# MCU_144_IOs.net
KiCad netlist of a schematic drawn in Altium Designer
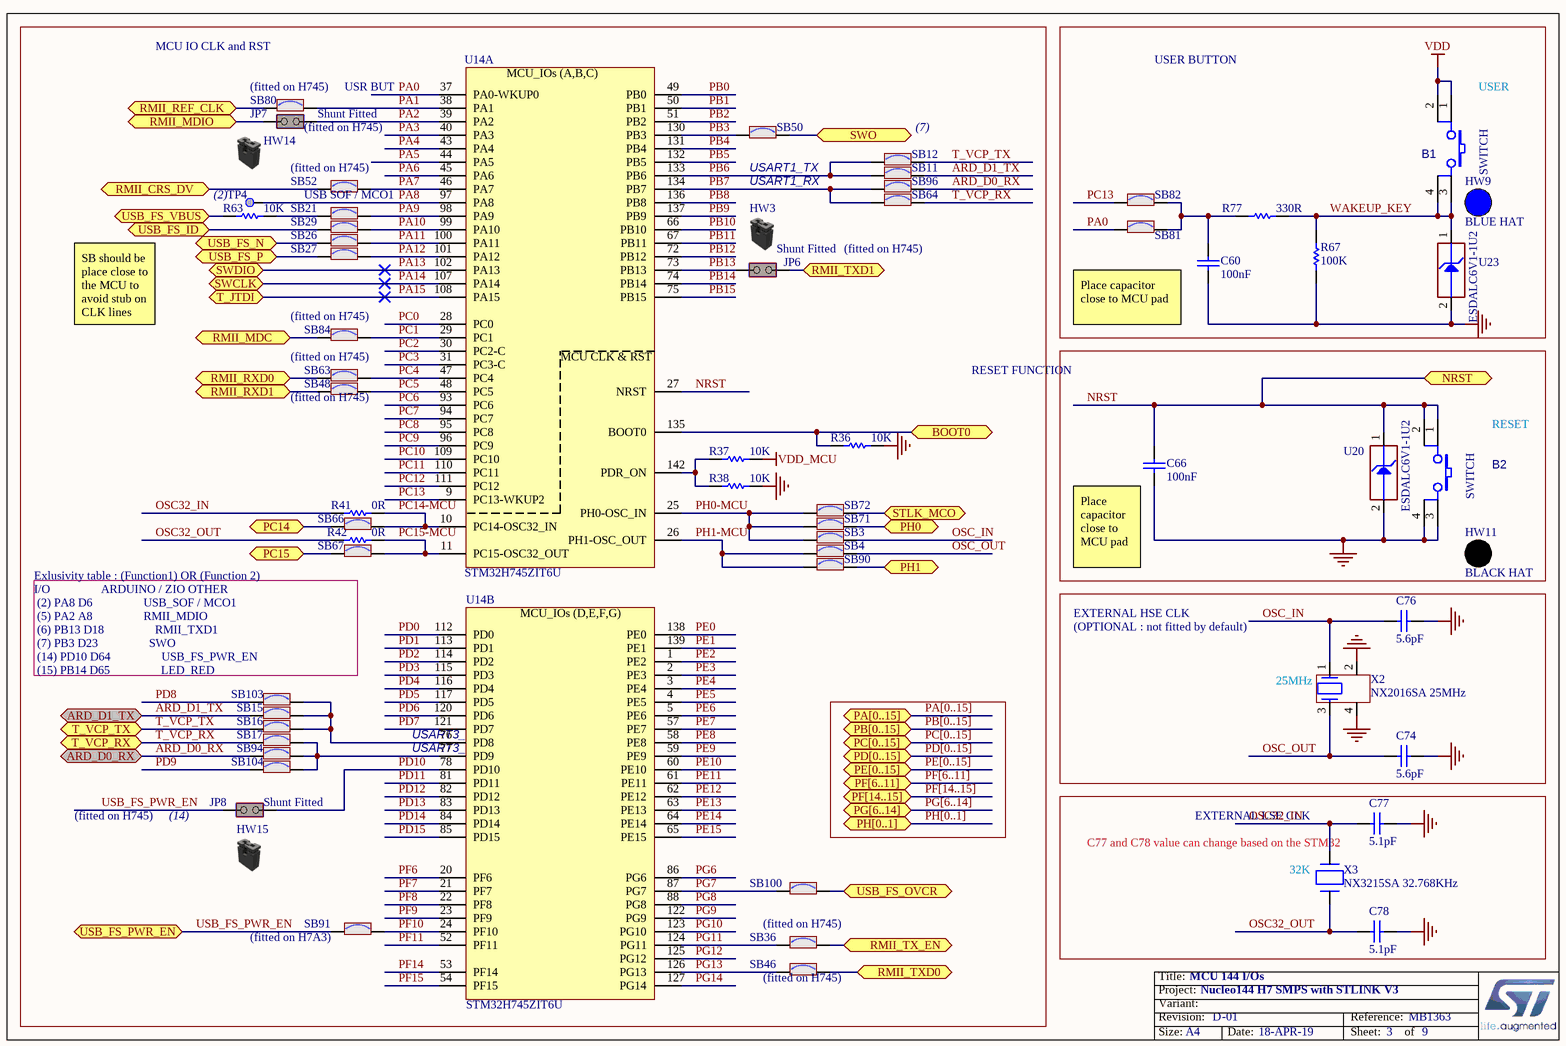
[diagram p0: MCU_144_IOs.SchDoc]

(export (version "E")
  (design (tool "Eeschema 10.0.6"))
  (components
    (comp (ref "B1")
      (value "SWITCH")
      (footprint "SWI_WEALTHMETAL_TD-0341_4P_BLUE")
      (description "Non-Open Push-Button 0.1A 24V")
      (fields
        (field (name "INTERNAL_PART_NUMBER") "MCD-00002")
        (field (name "MANUFACTURER_PART_NUMBER") "TD-0341")
        (field (name "PROVIDED_BY") "SUBCO")
      )
      (libsource (lib "MCD_PARTS_database") (part "SW-PUSH-CMS"))
    )
    (comp (ref "B2")
      (value "SWITCH")
      (footprint "SWI_WEALTHMETAL_TD-0341_4P_BLACK")
      (description "Non-Open Push-Button 0.1A 24V BLACK")
      (fields
        (field (name "INTERNAL_PART_NUMBER") "MCD-00001")
        (field (name "MANUFACTURER_PART_NUMBER") "TD-0341")
        (field (name "PROVIDED_BY") "SUBCO")
      )
      (libsource (lib "MCD_PARTS_database") (part "SW-PUSH-CMS"))
    )
    (comp (ref "C60")
      (value "100nF")
      (footprint "C0603")
      (description "Capacitor, MLCC, 100nF, 6V3, X5R, 10%, 0603, T=0,8mm")
      (fields
        (field (name "INTERNAL_PART_NUMBER") "MCD-00237")
        (field (name "MANUFACTURER_PART_NUMBER") "CC0603KRX5R5BB104")
        (field (name "PROVIDED_BY") "SUBCO")
      )
      (libsource (lib "MCD_PARTS_database") (part "Capacitor"))
    )
    (comp (ref "C66")
      (value "100nF")
      (footprint "C0603")
      (description "Capacitor, MLCC, 100nF, 6V3, X5R, 10%, 0603, T=0,8mm")
      (fields
        (field (name "INTERNAL_PART_NUMBER") "MCD-00237")
        (field (name "MANUFACTURER_PART_NUMBER") "CC0603KRX5R5BB104")
        (field (name "PROVIDED_BY") "SUBCO")
      )
      (libsource (lib "MCD_PARTS_database") (part "Capacitor"))
    )
    (comp (ref "C74")
      (value "5.6pF")
      (footprint "C0402")
      (description "Capacitor, MLCC, 5.6pF, 50V, NPO, 5%, 0402, T=0,5mm")
      (fields
        (field (name "INTERNAL_PART_NUMBER") "MCD-01374")
        (field (name "MANUFACTURER_PART_NUMBER") "CC0402BRNPO9BN5R6")
        (field (name "PROVIDED_BY") "SUBCO")
      )
      (libsource (lib "MCD_PARTS_database") (part "Capacitor"))
    )
    (comp (ref "C76")
      (value "5.6pF")
      (footprint "C0402")
      (description "Capacitor, MLCC, 5.6pF, 50V, NPO, 5%, 0402, T=0,5mm")
      (fields
        (field (name "INTERNAL_PART_NUMBER") "MCD-01374")
        (field (name "MANUFACTURER_PART_NUMBER") "CC0402BRNPO9BN5R6")
        (field (name "PROVIDED_BY") "SUBCO")
      )
      (libsource (lib "MCD_PARTS_database") (part "Capacitor"))
    )
    (comp (ref "C77")
      (value "5.1pF")
      (footprint "C0603")
      (description "Capacitor,5.1pF,0.25pF,50V,NPO,0603")
      (fields
        (field (name "INTERNAL_PART_NUMBER") "MCD-01367")
        (field (name "MANUFACTURER_PART_NUMBER") "CC0603CRNPO9BN5R1")
        (field (name "PROVIDED_BY") "SUBCO")
      )
      (libsource (lib "MCD_PARTS_database") (part "Capacitor"))
    )
    (comp (ref "C78")
      (value "5.1pF")
      (footprint "C0603")
      (description "Capacitor,5.1pF,0.25pF,50V,NPO,0603")
      (fields
        (field (name "INTERNAL_PART_NUMBER") "MCD-01367")
        (field (name "MANUFACTURER_PART_NUMBER") "CC0603CRNPO9BN5R1")
        (field (name "PROVIDED_BY") "SUBCO")
      )
      (libsource (lib "MCD_PARTS_database") (part "Capacitor"))
    )
    (comp (ref "HW3")
      (value "Shunt Black 2.54mm")
      (description "SHUNT 2.54mm BLACK")
      (fields
        (field (name "INTERNAL_PART_NUMBER") "MCD-00043")
        (field (name "MANUFACTURER_PART_NUMBER") "SNT-100-BK-G")
        (field (name "PROVIDED_BY") "SUBCO")
      )
      (libsource (lib "MCD_PARTS_database") (part "Shunt Black 2.54mm"))
    )
    (comp (ref "HW9")
      (value "BLUE HAT")
      (description "Blue Hat for switch TD0341X-G01-BLU")
      (fields
        (field (name "INTERNAL_PART_NUMBER") "MCD-00634")
        (field (name "MANUFACTURER_PART_NUMBER") "988.16.09.3.00002_SH-517")
        (field (name "PROVIDED_BY") "SUBCO")
      )
      (libsource (lib "MCD_PARTS_database") (part "BUTTON_HAT_BLUE"))
    )
    (comp (ref "HW11")
      (value "BLACK HAT")
      (description "Black Hat for switch TD0341X-G01-BLA")
      (fields
        (field (name "INTERNAL_PART_NUMBER") "MCD-00635")
        (field (name "MANUFACTURER_PART_NUMBER") "988.16.09.3.00003_SH-517")
        (field (name "PROVIDED_BY") "SUBCO")
      )
      (libsource (lib "MCD_PARTS_database") (part "BUTTON_HAT_BLACK"))
    )
    (comp (ref "HW14")
      (value "Shunt Black 2.54mm")
      (description "SHUNT 2.54mm BLACK")
      (fields
        (field (name "INTERNAL_PART_NUMBER") "MCD-00043")
        (field (name "MANUFACTURER_PART_NUMBER") "SNT-100-BK-G")
        (field (name "PROVIDED_BY") "SUBCO")
      )
      (libsource (lib "MCD_PARTS_database") (part "Shunt Black 2.54mm"))
    )
    (comp (ref "HW15")
      (value "Shunt Black 2.54mm")
      (description "SHUNT 2.54mm BLACK")
      (fields
        (field (name "INTERNAL_PART_NUMBER") "MCD-00043")
        (field (name "MANUFACTURER_PART_NUMBER") "SNT-100-BK-G")
        (field (name "PROVIDED_BY") "SUBCO")
      )
      (libsource (lib "MCD_PARTS_database") (part "Shunt Black 2.54mm"))
    )
    (comp (ref "JP6")
      (value "Shunt Fitted")
      (footprint "CON_SAMTEC_TSW-102-07-G-S")
      (description "Header, 2x1, 2,54mm, VR, TH, Height 5.84mm/2.54mm - Shunt Fitted by default")
      (fields
        (field (name "INTERNAL_PART_NUMBER") "MCD-00683")
        (field (name "MANUFACTURER_PART_NUMBER") "TSW-102-07-x-S")
        (field (name "PROVIDED_BY") "SUBCO")
      )
      (libsource (lib "MCD_PARTS_database") (part "Jumper_Header 2x1 Fitted"))
    )
    (comp (ref "JP7")
      (value "Shunt Fitted")
      (footprint "CON_SAMTEC_TSW-102-07-G-S")
      (description "Header, 2x1, 2,54mm, VR, TH, Height 5.84mm/2.54mm - Shunt Fitted by default")
      (fields
        (field (name "INTERNAL_PART_NUMBER") "MCD-00683")
        (field (name "MANUFACTURER_PART_NUMBER") "TSW-102-07-x-S")
        (field (name "PROVIDED_BY") "SUBCO")
      )
      (libsource (lib "MCD_PARTS_database") (part "Jumper_Header 2x1 Fitted"))
    )
    (comp (ref "JP8")
      (value "Shunt Fitted")
      (footprint "CON_SAMTEC_TSW-102-07-G-S")
      (description "Header, 2x1, 2,54mm, VR, TH, Height 5.84mm/2.54mm - Shunt Fitted by default")
      (fields
        (field (name "INTERNAL_PART_NUMBER") "MCD-00683")
        (field (name "MANUFACTURER_PART_NUMBER") "TSW-102-07-x-S")
        (field (name "PROVIDED_BY") "SUBCO")
      )
      (libsource (lib "MCD_PARTS_database") (part "Jumper_Header 2x1 Fitted"))
    )
    (comp (ref "R36")
      (value "10K")
      (footprint "R0603")
      (description "Resistor,10K,0603,1%,1/10W")
      (fields
        (field (name "INTERNAL_PART_NUMBER") "MCD-00220")
        (field (name "MANUFACTURER_PART_NUMBER") "RC0603FR-0710KL")
        (field (name "PROVIDED_BY") "SUBCO")
      )
      (libsource (lib "MCD_PARTS_database") (part "Resistor"))
    )
    (comp (ref "R37")
      (value "10K")
      (footprint "R0603")
      (description "Resistor,10K,0603,1%,1/10W")
      (fields
        (field (name "INTERNAL_PART_NUMBER") "MCD-00220")
        (field (name "MANUFACTURER_PART_NUMBER") "RC0603FR-0710KL")
        (field (name "PROVIDED_BY") "SUBCO")
      )
      (libsource (lib "MCD_PARTS_database") (part "Resistor"))
    )
    (comp (ref "R38")
      (value "10K")
      (footprint "R0603")
      (description "Resistor,10K,0603,1%,1/10W")
      (fields
        (field (name "INTERNAL_PART_NUMBER") "MCD-00220")
        (field (name "MANUFACTURER_PART_NUMBER") "RC0603FR-0710KL")
        (field (name "PROVIDED_BY") "SUBCO")
      )
      (libsource (lib "MCD_PARTS_database") (part "Resistor"))
    )
    (comp (ref "R41")
      (value "0R")
      (footprint "R0603")
      (description "Resistor,0R,0603,5%,1/10W")
      (fields
        (field (name "INTERNAL_PART_NUMBER") "MCD-00056")
        (field (name "MANUFACTURER_PART_NUMBER") "RC0603JR-070RL")
        (field (name "PROVIDED_BY") "SUBCO")
      )
      (libsource (lib "MCD_PARTS_database") (part "Resistor"))
    )
    (comp (ref "R42")
      (value "0R")
      (footprint "R0603")
      (description "Resistor,0R,0603,5%,1/10W")
      (fields
        (field (name "INTERNAL_PART_NUMBER") "MCD-00056")
        (field (name "MANUFACTURER_PART_NUMBER") "RC0603JR-070RL")
        (field (name "PROVIDED_BY") "SUBCO")
      )
      (libsource (lib "MCD_PARTS_database") (part "Resistor"))
    )
    (comp (ref "R63")
      (value "10K")
      (footprint "R0402")
      (description "Resistor,10K,0402,1%,1/16W")
      (fields
        (field (name "INTERNAL_PART_NUMBER") "MCD-00053")
        (field (name "MANUFACTURER_PART_NUMBER") "RC0402FR-0710KL")
        (field (name "PROVIDED_BY") "SUBCO")
      )
      (libsource (lib "MCD_PARTS_database") (part "Resistor"))
    )
    (comp (ref "R67")
      (value "100K")
      (footprint "R0603")
      (description "Resistor,100K,0603,1%,1/10W")
      (fields
        (field (name "INTERNAL_PART_NUMBER") "MCD-00223")
        (field (name "MANUFACTURER_PART_NUMBER") "RC0603FR-07100KL")
        (field (name "PROVIDED_BY") "SUBCO")
      )
      (libsource (lib "MCD_PARTS_database") (part "Resistor"))
    )
    (comp (ref "R77")
      (value "330R")
      (footprint "R0603")
      (description "Resistor,330R,0603,1%,1/10W")
      (fields
        (field (name "INTERNAL_PART_NUMBER") "MCD-00197")
        (field (name "MANUFACTURER_PART_NUMBER") "RC0603FR-07330RL")
        (field (name "PROVIDED_BY") "SUBCO")
      )
      (libsource (lib "MCD_PARTS_database") (part "Resistor"))
    )
    (comp (ref "SB3")
      (value "SB_ON")
      (footprint "SOLDER-BRIDGE_R0603-0R")
      (description "Solder Bridge ON")
      (fields
        (field (name "INTERNAL_PART_NUMBER") "MCD-00071")
        (field (name "MANUFACTURER_PART_NUMBER") "RC0603JR-070RL")
        (field (name "PROVIDED_BY") "SUBCO")
      )
      (libsource (lib "MCD_PARTS_database") (part "SB_ON"))
    )
    (comp (ref "SB4")
      (value "SB_ON")
      (footprint "SOLDER-BRIDGE_R0603-0R")
      (description "Solder Bridge ON")
      (fields
        (field (name "INTERNAL_PART_NUMBER") "MCD-00071")
        (field (name "MANUFACTURER_PART_NUMBER") "RC0603JR-070RL")
        (field (name "PROVIDED_BY") "SUBCO")
      )
      (libsource (lib "MCD_PARTS_database") (part "SB_ON"))
    )
    (comp (ref "SB11")
      (value "SB_ON")
      (footprint "SOLDER-BRIDGE_R0603-0R")
      (description "Solder Bridge ON")
      (fields
        (field (name "INTERNAL_PART_NUMBER") "MCD-00071")
        (field (name "MANUFACTURER_PART_NUMBER") "RC0603JR-070RL")
        (field (name "PROVIDED_BY") "SUBCO")
      )
      (libsource (lib "") (part "SB_ON_1"))
    )
    (comp (ref "SB12")
      (value "SB_ON")
      (footprint "SOLDER-BRIDGE_R0603-0R")
      (description "Solder Bridge ON")
      (fields
        (field (name "INTERNAL_PART_NUMBER") "MCD-00071")
        (field (name "MANUFACTURER_PART_NUMBER") "RC0603JR-070RL")
        (field (name "PROVIDED_BY") "SUBCO")
      )
      (libsource (lib "") (part "SB_ON_1"))
    )
    (comp (ref "SB15")
      (value "SB_ON")
      (footprint "SOLDER-BRIDGE_R0603-0R")
      (description "Solder Bridge ON")
      (fields
        (field (name "INTERNAL_PART_NUMBER") "MCD-00071")
        (field (name "MANUFACTURER_PART_NUMBER") "RC0603JR-070RL")
        (field (name "PROVIDED_BY") "SUBCO")
      )
      (libsource (lib "") (part "SB_ON_1"))
    )
    (comp (ref "SB16")
      (value "SB_ON")
      (footprint "SOLDER-BRIDGE_R0603-0R")
      (description "Solder Bridge ON")
      (fields
        (field (name "INTERNAL_PART_NUMBER") "MCD-00071")
        (field (name "MANUFACTURER_PART_NUMBER") "RC0603JR-070RL")
        (field (name "PROVIDED_BY") "SUBCO")
      )
      (libsource (lib "") (part "SB_ON_1"))
    )
    (comp (ref "SB17")
      (value "SB_ON")
      (footprint "SOLDER-BRIDGE_R0603-0R")
      (description "Solder Bridge ON")
      (fields
        (field (name "INTERNAL_PART_NUMBER") "MCD-00071")
        (field (name "MANUFACTURER_PART_NUMBER") "RC0603JR-070RL")
        (field (name "PROVIDED_BY") "SUBCO")
      )
      (libsource (lib "") (part "SB_ON_1"))
    )
    (comp (ref "SB21")
      (value "SB_ON")
      (footprint "SOLDER-BRIDGE_R0603-0R")
      (description "Solder Bridge ON")
      (fields
        (field (name "INTERNAL_PART_NUMBER") "MCD-00071")
        (field (name "MANUFACTURER_PART_NUMBER") "RC0603JR-070RL")
        (field (name "PROVIDED_BY") "SUBCO")
      )
      (libsource (lib "") (part "SB_ON_1"))
    )
    (comp (ref "SB26")
      (value "SB_ON")
      (footprint "SOLDER-BRIDGE_R0603-0R")
      (description "Solder Bridge ON")
      (fields
        (field (name "INTERNAL_PART_NUMBER") "MCD-00071")
        (field (name "MANUFACTURER_PART_NUMBER") "RC0603JR-070RL")
        (field (name "PROVIDED_BY") "SUBCO")
      )
      (libsource (lib "") (part "SB_ON_1"))
    )
    (comp (ref "SB27")
      (value "SB_ON")
      (footprint "SOLDER-BRIDGE_R0603-0R")
      (description "Solder Bridge ON")
      (fields
        (field (name "INTERNAL_PART_NUMBER") "MCD-00071")
        (field (name "MANUFACTURER_PART_NUMBER") "RC0603JR-070RL")
        (field (name "PROVIDED_BY") "SUBCO")
      )
      (libsource (lib "") (part "SB_ON_1"))
    )
    (comp (ref "SB29")
      (value "SB_ON")
      (footprint "SOLDER-BRIDGE_R0603-0R")
      (description "Solder Bridge ON")
      (fields
        (field (name "INTERNAL_PART_NUMBER") "MCD-00071")
        (field (name "MANUFACTURER_PART_NUMBER") "RC0603JR-070RL")
        (field (name "PROVIDED_BY") "SUBCO")
      )
      (libsource (lib "") (part "SB_ON_1"))
    )
    (comp (ref "SB36")
      (value "SB_ON")
      (footprint "SOLDER-BRIDGE_R0603-0R")
      (description "Solder Bridge ON")
      (fields
        (field (name "INTERNAL_PART_NUMBER") "MCD-00071")
        (field (name "MANUFACTURER_PART_NUMBER") "RC0603JR-070RL")
        (field (name "PROVIDED_BY") "SUBCO")
      )
      (libsource (lib "") (part "SB_ON_1"))
    )
    (comp (ref "SB46")
      (value "SB_ON")
      (footprint "SOLDER-BRIDGE_R0603-0R")
      (description "Solder Bridge ON")
      (fields
        (field (name "INTERNAL_PART_NUMBER") "MCD-00071")
        (field (name "MANUFACTURER_PART_NUMBER") "RC0603JR-070RL")
        (field (name "PROVIDED_BY") "SUBCO")
      )
      (libsource (lib "") (part "SB_ON_1"))
    )
    (comp (ref "SB48")
      (value "SB_ON")
      (footprint "SOLDER-BRIDGE_R0603-0R")
      (description "Solder Bridge ON")
      (fields
        (field (name "INTERNAL_PART_NUMBER") "MCD-00071")
        (field (name "MANUFACTURER_PART_NUMBER") "RC0603JR-070RL")
        (field (name "PROVIDED_BY") "SUBCO")
      )
      (libsource (lib "MCD_PARTS_database") (part "SB_ON"))
    )
    (comp (ref "SB50")
      (value "SB_ON")
      (footprint "SOLDER-BRIDGE_R0603-0R")
      (description "Solder Bridge ON")
      (fields
        (field (name "INTERNAL_PART_NUMBER") "MCD-00071")
        (field (name "MANUFACTURER_PART_NUMBER") "RC0603JR-070RL")
        (field (name "PROVIDED_BY") "SUBCO")
      )
      (libsource (lib "") (part "SB_ON_1"))
    )
    (comp (ref "SB52")
      (value "SB_ON")
      (footprint "SOLDER-BRIDGE_R0603-0R")
      (description "Solder Bridge ON")
      (fields
        (field (name "INTERNAL_PART_NUMBER") "MCD-00071")
        (field (name "MANUFACTURER_PART_NUMBER") "RC0603JR-070RL")
        (field (name "PROVIDED_BY") "SUBCO")
      )
      (libsource (lib "") (part "SB_ON_1"))
    )
    (comp (ref "SB63")
      (value "SB_ON")
      (footprint "SOLDER-BRIDGE_R0603-0R")
      (description "Solder Bridge ON")
      (fields
        (field (name "INTERNAL_PART_NUMBER") "MCD-00071")
        (field (name "MANUFACTURER_PART_NUMBER") "RC0603JR-070RL")
        (field (name "PROVIDED_BY") "SUBCO")
      )
      (libsource (lib "MCD_PARTS_database") (part "SB_ON"))
    )
    (comp (ref "SB64")
      (value "SB_ON")
      (footprint "SOLDER-BRIDGE_R0603-0R")
      (description "Solder Bridge ON")
      (fields
        (field (name "INTERNAL_PART_NUMBER") "MCD-00071")
        (field (name "MANUFACTURER_PART_NUMBER") "RC0603JR-070RL")
        (field (name "PROVIDED_BY") "SUBCO")
      )
      (libsource (lib "") (part "SB_ON_1"))
    )
    (comp (ref "SB66")
      (value "SB_ON")
      (footprint "SOLDER-BRIDGE_R0603-0R")
      (description "Solder Bridge ON")
      (fields
        (field (name "INTERNAL_PART_NUMBER") "MCD-00071")
        (field (name "MANUFACTURER_PART_NUMBER") "RC0603JR-070RL")
        (field (name "PROVIDED_BY") "SUBCO")
      )
      (libsource (lib "MCD_PARTS_database") (part "SB_ON"))
    )
    (comp (ref "SB67")
      (value "SB_ON")
      (footprint "SOLDER-BRIDGE_R0603-0R")
      (description "Solder Bridge ON")
      (fields
        (field (name "INTERNAL_PART_NUMBER") "MCD-00071")
        (field (name "MANUFACTURER_PART_NUMBER") "RC0603JR-070RL")
        (field (name "PROVIDED_BY") "SUBCO")
      )
      (libsource (lib "MCD_PARTS_database") (part "SB_ON"))
    )
    (comp (ref "SB71")
      (value "SB_ON")
      (footprint "SOLDER-BRIDGE_R0603-0R")
      (description "Solder Bridge ON")
      (fields
        (field (name "INTERNAL_PART_NUMBER") "MCD-00071")
        (field (name "MANUFACTURER_PART_NUMBER") "RC0603JR-070RL")
        (field (name "PROVIDED_BY") "SUBCO")
      )
      (libsource (lib "MCD_PARTS_database") (part "SB_ON"))
    )
    (comp (ref "SB72")
      (value "SB_ON")
      (footprint "SOLDER-BRIDGE_R0603-0R")
      (description "Solder Bridge ON")
      (fields
        (field (name "INTERNAL_PART_NUMBER") "MCD-00071")
        (field (name "MANUFACTURER_PART_NUMBER") "RC0603JR-070RL")
        (field (name "PROVIDED_BY") "SUBCO")
      )
      (libsource (lib "MCD_PARTS_database") (part "SB_ON"))
    )
    (comp (ref "SB80")
      (value "SB_ON")
      (footprint "SOLDER-BRIDGE_R0603-0R")
      (description "Solder Bridge ON")
      (fields
        (field (name "INTERNAL_PART_NUMBER") "MCD-00071")
        (field (name "MANUFACTURER_PART_NUMBER") "RC0603JR-070RL")
        (field (name "PROVIDED_BY") "SUBCO")
      )
      (libsource (lib "") (part "SB_ON_1"))
    )
    (comp (ref "SB81")
      (value "SB_ON")
      (footprint "SOLDER-BRIDGE_R0603-0R")
      (description "Solder Bridge ON")
      (fields
        (field (name "INTERNAL_PART_NUMBER") "MCD-00071")
        (field (name "MANUFACTURER_PART_NUMBER") "RC0603JR-070RL")
        (field (name "PROVIDED_BY") "SUBCO")
      )
      (libsource (lib "") (part "SB_ON_1"))
    )
    (comp (ref "SB82")
      (value "SB_ON")
      (footprint "SOLDER-BRIDGE_R0603-0R")
      (description "Solder Bridge ON")
      (fields
        (field (name "INTERNAL_PART_NUMBER") "MCD-00071")
        (field (name "MANUFACTURER_PART_NUMBER") "RC0603JR-070RL")
        (field (name "PROVIDED_BY") "SUBCO")
      )
      (libsource (lib "") (part "SB_ON_1"))
    )
    (comp (ref "SB84")
      (value "SB_ON")
      (footprint "SOLDER-BRIDGE_R0603-0R")
      (description "Solder Bridge ON")
      (fields
        (field (name "INTERNAL_PART_NUMBER") "MCD-00071")
        (field (name "MANUFACTURER_PART_NUMBER") "RC0603JR-070RL")
        (field (name "PROVIDED_BY") "SUBCO")
      )
      (libsource (lib "MCD_PARTS_database") (part "SB_ON"))
    )
    (comp (ref "SB90")
      (value "SB_ON")
      (footprint "SOLDER-BRIDGE_R0603-0R")
      (description "Solder Bridge ON")
      (fields
        (field (name "INTERNAL_PART_NUMBER") "MCD-00071")
        (field (name "MANUFACTURER_PART_NUMBER") "RC0603JR-070RL")
        (field (name "PROVIDED_BY") "SUBCO")
      )
      (libsource (lib "MCD_PARTS_database") (part "SB_ON"))
    )
    (comp (ref "SB91")
      (value "SB_ON")
      (footprint "SOLDER-BRIDGE_R0603-0R")
      (description "Solder Bridge ON")
      (fields
        (field (name "INTERNAL_PART_NUMBER") "MCD-00071")
        (field (name "MANUFACTURER_PART_NUMBER") "RC0603JR-070RL")
        (field (name "PROVIDED_BY") "SUBCO")
      )
      (libsource (lib "") (part "SB_ON_1"))
    )
    (comp (ref "SB94")
      (value "SB_ON")
      (footprint "SOLDER-BRIDGE_R0603-0R")
      (description "Solder Bridge ON")
      (fields
        (field (name "INTERNAL_PART_NUMBER") "MCD-00071")
        (field (name "MANUFACTURER_PART_NUMBER") "RC0603JR-070RL")
        (field (name "PROVIDED_BY") "SUBCO")
      )
      (libsource (lib "") (part "SB_ON_1"))
    )
    (comp (ref "SB96")
      (value "SB_ON")
      (footprint "SOLDER-BRIDGE_R0603-0R")
      (description "Solder Bridge ON")
      (fields
        (field (name "INTERNAL_PART_NUMBER") "MCD-00071")
        (field (name "MANUFACTURER_PART_NUMBER") "RC0603JR-070RL")
        (field (name "PROVIDED_BY") "SUBCO")
      )
      (libsource (lib "") (part "SB_ON_1"))
    )
    (comp (ref "SB100")
      (value "SB_ON")
      (footprint "SOLDER-BRIDGE_R0603-0R")
      (description "Solder Bridge ON")
      (fields
        (field (name "INTERNAL_PART_NUMBER") "MCD-00071")
        (field (name "MANUFACTURER_PART_NUMBER") "RC0603JR-070RL")
        (field (name "PROVIDED_BY") "SUBCO")
      )
      (libsource (lib "") (part "SB_ON_1"))
    )
    (comp (ref "SB103")
      (value "SB_ON")
      (footprint "SOLDER-BRIDGE_R0603-0R")
      (description "Solder Bridge ON")
      (fields
        (field (name "INTERNAL_PART_NUMBER") "MCD-00071")
        (field (name "MANUFACTURER_PART_NUMBER") "RC0603JR-070RL")
        (field (name "PROVIDED_BY") "SUBCO")
      )
      (libsource (lib "MCD_PARTS_database") (part "SB_ON"))
    )
    (comp (ref "SB104")
      (value "SB_ON")
      (footprint "SOLDER-BRIDGE_R0603-0R")
      (description "Solder Bridge ON")
      (fields
        (field (name "INTERNAL_PART_NUMBER") "MCD-00071")
        (field (name "MANUFACTURER_PART_NUMBER") "RC0603JR-070RL")
        (field (name "PROVIDED_BY") "SUBCO")
      )
      (libsource (lib "MCD_PARTS_database") (part "SB_ON"))
    )
    (comp (ref "TP4")
      (value "Test Point")
      (footprint "TP_SMD_1MM")
      (description "Test Point 1mm")
      (fields
        (field (name "INTERNAL_PART_NUMBER") "MCD-00074")
        (field (name "MANUFACTURER_PART_NUMBER") "n/a")
      )
      (libsource (lib "MCD_PARTS_database") (part "Test Point"))
    )
    (comp (ref "U14")
      (value "STM32H745ZIT6U")
      (footprint "ICC_LQFP144_20X20_P050_SOCKET_YAMAICHI_IC149-144-145-B5_NM")
      (description "STM32H745ZIT6U, LQFP144 package, 20x20, with socket footprint")
      (fields
        (field (name "INTERNAL_PART_NUMBER") "MCD-01401")
        (field (name "MANUFACTURER") "STMICROELECTRONICS")
        (field (name "PROVIDED_BY") "SUBCO with ST control")
      )
      (libsource (lib "MCD_PARTS_database") (part "STM32H7_LQFP144_SMPS"))
    )
    (comp (ref "U20")
      (value "ESDALC6V1-1U2")
      (footprint "ESD_ST0201")
      (description "ESD protection 6V1")
      (fields
        (field (name "INTERNAL_PART_NUMBER") "MCD-00170")
        (field (name "MANUFACTURER") "STMICROELECTRONICS")
        (field (name "PROVIDED_BY") "SUBCO with ST control")
      )
      (libsource (lib "MCD_PARTS_database") (part "ESD-TRANSIL"))
    )
    (comp (ref "U23")
      (value "ESDALC6V1-1U2")
      (footprint "ESD_ST0201")
      (description "ESD protection 6V1")
      (fields
        (field (name "INTERNAL_PART_NUMBER") "MCD-00170")
        (field (name "MANUFACTURER") "STMICROELECTRONICS")
        (field (name "PROVIDED_BY") "SUBCO with ST control")
      )
      (libsource (lib "MCD_PARTS_database") (part "ESD-TRANSIL"))
    )
    (comp (ref "X2")
      (value "NX2016SA 25MHz")
      (footprint "CRY_NX2016SA_4P")
      (description "Crystal 25MHz, 6pF, +-20ppm, 80ohms max, SMD")
      (fields
        (field (name "INTERNAL_PART_NUMBER") "MCD-01364")
        (field (name "MANUFACTURER_PART_NUMBER") "NX2016SA 25MHz EXS00A-CS11321")
        (field (name "PROVIDED_BY") "SUBCO")
      )
      (libsource (lib "MCD_PARTS_database") (part "XTAL_4_PINS"))
    )
    (comp (ref "X3")
      (value "NX3215SA 32.768KHz")
      (footprint "CRY_NX3215SA_2P")
      (description "Crystal 32.768kHz, 6pF, +-20ppm, 50Kohms max, SMD")
      (fields
        (field (name "INTERNAL_PART_NUMBER") "MCD-00091")
        (field (name "MANUFACTURER_PART_NUMBER") "NX3215SA 32.768KHz EXS00A-MU00525")
        (field (name "PROVIDED_BY") "SUBCO")
      )
      (libsource (lib "MCD_PARTS_database") (part "XTAL_2_PINS"))
    )
  )
  (nets
    (net (code "1") (name "/ARD_D0_RX") (class "Default")
      (node (ref "SB94") (pin "2") (pinfunction "2_2") (pintype "passive"))
      (node (ref "SB96") (pin "1") (pinfunction "1_1") (pintype "passive"))
    )
    (net (code "2") (name "/ARD_D1_TX") (class "Default")
      (node (ref "SB11") (pin "1") (pinfunction "1_1") (pintype "passive"))
      (node (ref "SB15") (pin "2") (pinfunction "2_2") (pintype "passive"))
    )
    (net (code "3") (name "/BOOT0") (class "Default")
      (node (ref "R36") (pin "1") (pinfunction "1_1") (pintype "passive"))
      (node (ref "U14") (pin "135") (pinfunction "BOOT0_135") (pintype "passive"))
    )
    (net (code "4") (name "/NRST") (class "Default")
      (node (ref "B2") (pin "1") (pinfunction "1_1") (pintype "passive"))
      (node (ref "B2") (pin "2") (pinfunction "2_2") (pintype "passive"))
      (node (ref "C66") (pin "2") (pinfunction "2_2") (pintype "passive"))
      (node (ref "U14") (pin "27") (pinfunction "NRST_27") (pintype "passive"))
      (node (ref "U20") (pin "1") (pinfunction "IO1_1") (pintype "passive"))
    )
    (net (code "5") (name "/OSC32_IN") (class "Default")
      (node (ref "C77") (pin "1") (pinfunction "1_1") (pintype "passive"))
      (node (ref "R41") (pin "2") (pinfunction "2_2") (pintype "passive"))
      (node (ref "X3") (pin "2") (pinfunction "X2_2") (pintype "passive"))
    )
    (net (code "6") (name "/OSC32_OUT") (class "Default")
      (node (ref "C78") (pin "1") (pinfunction "1_1") (pintype "passive"))
      (node (ref "R42") (pin "1") (pinfunction "1_1") (pintype "passive"))
      (node (ref "X3") (pin "1") (pinfunction "X1_1") (pintype "passive"))
    )
    (net (code "7") (name "/OSC_IN") (class "Default")
      (node (ref "C76") (pin "1") (pinfunction "1_1") (pintype "passive"))
      (node (ref "SB3") (pin "2") (pinfunction "2_2") (pintype "passive"))
      (node (ref "X2") (pin "1") (pinfunction "1_1") (pintype "passive"))
    )
    (net (code "8") (name "/OSC_OUT") (class "Default")
      (node (ref "C74") (pin "1") (pinfunction "1_1") (pintype "passive"))
      (node (ref "SB4") (pin "2") (pinfunction "2_2") (pintype "passive"))
      (node (ref "X2") (pin "3") (pinfunction "3_3") (pintype "passive"))
    )
    (net (code "9") (name "/PA0") (class "Default")
      (node (ref "SB81") (pin "2") (pinfunction "2_2") (pintype "passive"))
      (node (ref "U14") (pin "37") (pinfunction "PA0-WKUP0_37") (pintype "passive"))
    )
    (net (code "10") (name "/PA1") (class "Default")
      (node (ref "SB80") (pin "1") (pinfunction "1_1") (pintype "passive"))
      (node (ref "U14") (pin "38") (pinfunction "PA1_38") (pintype "passive"))
    )
    (net (code "11") (name "/PA2") (class "Default")
      (node (ref "JP7") (pin "2") (pinfunction "NO_2") (pintype "passive"))
      (node (ref "U14") (pin "39") (pinfunction "PA2_39") (pintype "passive"))
    )
    (net (code "12") (name "/PA3") (class "Default")
      (node (ref "U14") (pin "40") (pinfunction "PA3_40") (pintype "passive"))
    )
    (net (code "13") (name "/PA4") (class "Default")
      (node (ref "U14") (pin "43") (pinfunction "PA4_43") (pintype "passive"))
    )
    (net (code "14") (name "/PA5") (class "Default")
      (node (ref "U14") (pin "44") (pinfunction "PA5_44") (pintype "passive"))
    )
    (net (code "15") (name "/PA6") (class "Default")
      (node (ref "U14") (pin "45") (pinfunction "PA6_45") (pintype "passive"))
    )
    (net (code "16") (name "/PA7") (class "Default")
      (node (ref "SB52") (pin "1") (pinfunction "1_1") (pintype "passive"))
      (node (ref "U14") (pin "46") (pinfunction "PA7_46") (pintype "passive"))
    )
    (net (code "17") (name "/PA8") (class "Default")
      (node (ref "TP4") (pin "1") (pinfunction "1_1") (pintype "passive"))
      (node (ref "U14") (pin "97") (pinfunction "PA8_97") (pintype "passive"))
    )
    (net (code "18") (name "/PA9") (class "Default")
      (node (ref "SB21") (pin "1") (pinfunction "1_1") (pintype "passive"))
      (node (ref "U14") (pin "98") (pinfunction "PA9_98") (pintype "passive"))
    )
    (net (code "19") (name "/PA10") (class "Default")
      (node (ref "SB29") (pin "1") (pinfunction "1_1") (pintype "passive"))
      (node (ref "U14") (pin "99") (pinfunction "PA10_99") (pintype "passive"))
    )
    (net (code "20") (name "/PA11") (class "Default")
      (node (ref "SB26") (pin "1") (pinfunction "1_1") (pintype "passive"))
      (node (ref "U14") (pin "100") (pinfunction "PA11_100") (pintype "passive"))
    )
    (net (code "21") (name "/PA12") (class "Default")
      (node (ref "SB27") (pin "1") (pinfunction "1_1") (pintype "passive"))
      (node (ref "U14") (pin "101") (pinfunction "PA12_101") (pintype "passive"))
    )
    (net (code "22") (name "/PA13") (class "Default")
      (node (ref "U14") (pin "102") (pinfunction "PA13_102") (pintype "passive"))
    )
    (net (code "23") (name "/PA14") (class "Default")
      (node (ref "U14") (pin "107") (pinfunction "PA14_107") (pintype "passive"))
    )
    (net (code "24") (name "/PA15") (class "Default")
      (node (ref "U14") (pin "108") (pinfunction "PA15_108") (pintype "passive"))
    )
    (net (code "26") (name "/PB0") (class "Default")
      (node (ref "U14") (pin "49") (pinfunction "PB0_49") (pintype "passive"))
    )
    (net (code "27") (name "/PB1") (class "Default")
      (node (ref "U14") (pin "50") (pinfunction "PB1_50") (pintype "passive"))
    )
    (net (code "28") (name "/PB2") (class "Default")
      (node (ref "U14") (pin "51") (pinfunction "PB2_51") (pintype "passive"))
    )
    (net (code "29") (name "/PB3") (class "Default")
      (node (ref "SB50") (pin "2") (pinfunction "2_2") (pintype "passive"))
      (node (ref "U14") (pin "130") (pinfunction "PB3_130") (pintype "passive"))
    )
    (net (code "30") (name "/PB4") (class "Default")
      (node (ref "U14") (pin "131") (pinfunction "PB4_131") (pintype "passive"))
    )
    (net (code "31") (name "/PB5") (class "Default")
      (node (ref "U14") (pin "132") (pinfunction "PB5_132") (pintype "passive"))
    )
    (net (code "32") (name "/PB6") (class "Default")
      (node (ref "SB11") (pin "2") (pinfunction "2_2") (pintype "passive"))
      (node (ref "SB12") (pin "2") (pinfunction "2_2") (pintype "passive"))
      (node (ref "U14") (pin "133") (pinfunction "PB6_133") (pintype "passive"))
    )
    (net (code "33") (name "/PB7") (class "Default")
      (node (ref "SB64") (pin "2") (pinfunction "2_2") (pintype "passive"))
      (node (ref "SB96") (pin "2") (pinfunction "2_2") (pintype "passive"))
      (node (ref "U14") (pin "134") (pinfunction "PB7_134") (pintype "passive"))
    )
    (net (code "34") (name "/PB8") (class "Default")
      (node (ref "U14") (pin "136") (pinfunction "PB8_136") (pintype "passive"))
    )
    (net (code "35") (name "/PB9") (class "Default")
      (node (ref "U14") (pin "137") (pinfunction "PB9_137") (pintype "passive"))
    )
    (net (code "36") (name "/PB10") (class "Default")
      (node (ref "U14") (pin "66") (pinfunction "PB10_66") (pintype "passive"))
    )
    (net (code "37") (name "/PB11") (class "Default")
      (node (ref "U14") (pin "67") (pinfunction "PB11_67") (pintype "passive"))
    )
    (net (code "38") (name "/PB12") (class "Default")
      (node (ref "U14") (pin "72") (pinfunction "PB12_72") (pintype "passive"))
    )
    (net (code "39") (name "/PB13") (class "Default")
      (node (ref "JP6") (pin "1") (pinfunction "COMMON_1") (pintype "passive"))
      (node (ref "U14") (pin "73") (pinfunction "PB13_73") (pintype "passive"))
    )
    (net (code "40") (name "/PB14") (class "Default")
      (node (ref "U14") (pin "74") (pinfunction "PB14_74") (pintype "passive"))
    )
    (net (code "41") (name "/PB15") (class "Default")
      (node (ref "U14") (pin "75") (pinfunction "PB15_75") (pintype "passive"))
    )
    (net (code "43") (name "/PC0") (class "Default")
      (node (ref "U14") (pin "28") (pinfunction "PC0_28") (pintype "passive"))
    )
    (net (code "44") (name "/PC1") (class "Default")
      (node (ref "SB84") (pin "2") (pinfunction "2_2") (pintype "passive"))
      (node (ref "U14") (pin "29") (pinfunction "PC1_29") (pintype "passive"))
    )
    (net (code "45") (name "/PC2") (class "Default")
      (node (ref "U14") (pin "30") (pinfunction "PC2-C_30") (pintype "passive"))
    )
    (net (code "46") (name "/PC3") (class "Default")
      (node (ref "U14") (pin "31") (pinfunction "PC3-C_31") (pintype "passive"))
    )
    (net (code "47") (name "/PC4") (class "Default")
      (node (ref "SB63") (pin "2") (pinfunction "2_2") (pintype "passive"))
      (node (ref "U14") (pin "47") (pinfunction "PC4_47") (pintype "passive"))
    )
    (net (code "48") (name "/PC5") (class "Default")
      (node (ref "SB48") (pin "2") (pinfunction "2_2") (pintype "passive"))
      (node (ref "U14") (pin "48") (pinfunction "PC5_48") (pintype "passive"))
    )
    (net (code "49") (name "/PC6") (class "Default")
      (node (ref "U14") (pin "93") (pinfunction "PC6_93") (pintype "passive"))
    )
    (net (code "50") (name "/PC7") (class "Default")
      (node (ref "U14") (pin "94") (pinfunction "PC7_94") (pintype "passive"))
    )
    (net (code "51") (name "/PC8") (class "Default")
      (node (ref "U14") (pin "95") (pinfunction "PC8_95") (pintype "passive"))
    )
    (net (code "52") (name "/PC9") (class "Default")
      (node (ref "U14") (pin "96") (pinfunction "PC9_96") (pintype "passive"))
    )
    (net (code "53") (name "/PC10") (class "Default")
      (node (ref "U14") (pin "109") (pinfunction "PC10_109") (pintype "passive"))
    )
    (net (code "54") (name "/PC11") (class "Default")
      (node (ref "U14") (pin "110") (pinfunction "PC11_110") (pintype "passive"))
    )
    (net (code "55") (name "/PC12") (class "Default")
      (node (ref "U14") (pin "111") (pinfunction "PC12_111") (pintype "passive"))
    )
    (net (code "56") (name "/PC13") (class "Default")
      (node (ref "SB82") (pin "2") (pinfunction "2_2") (pintype "passive"))
      (node (ref "U14") (pin "9") (pinfunction "PC13-WKUP2_9") (pintype "passive"))
    )
    (net (code "57") (name "/PC14") (class "Default")
      (node (ref "SB66") (pin "1") (pinfunction "1_1") (pintype "passive"))
    )
    (net (code "58") (name "/PC14-MCU") (class "Default")
      (node (ref "R41") (pin "1") (pinfunction "1_1") (pintype "passive"))
      (node (ref "SB66") (pin "2") (pinfunction "2_2") (pintype "passive"))
      (node (ref "U14") (pin "10") (pinfunction "PC14-OSC32_IN_10") (pintype "passive"))
    )
    (net (code "59") (name "/PC15") (class "Default")
      (node (ref "SB67") (pin "1") (pinfunction "1_1") (pintype "passive"))
    )
    (net (code "60") (name "/PC15-MCU") (class "Default")
      (node (ref "R42") (pin "2") (pinfunction "2_2") (pintype "passive"))
      (node (ref "SB67") (pin "2") (pinfunction "2_2") (pintype "passive"))
      (node (ref "U14") (pin "11") (pinfunction "PC15-OSC32_OUT_11") (pintype "passive"))
    )
    (net (code "62") (name "/PD0") (class "Default")
      (node (ref "U14") (pin "112") (pinfunction "PD0_112") (pintype "passive"))
    )
    (net (code "63") (name "/PD1") (class "Default")
      (node (ref "U14") (pin "113") (pinfunction "PD1_113") (pintype "passive"))
    )
    (net (code "64") (name "/PD2") (class "Default")
      (node (ref "U14") (pin "114") (pinfunction "PD2_114") (pintype "passive"))
    )
    (net (code "65") (name "/PD3") (class "Default")
      (node (ref "U14") (pin "115") (pinfunction "PD3_115") (pintype "passive"))
    )
    (net (code "66") (name "/PD4") (class "Default")
      (node (ref "U14") (pin "116") (pinfunction "PD4_116") (pintype "passive"))
    )
    (net (code "67") (name "/PD5") (class "Default")
      (node (ref "U14") (pin "117") (pinfunction "PD5_117") (pintype "passive"))
    )
    (net (code "68") (name "/PD6") (class "Default")
      (node (ref "U14") (pin "120") (pinfunction "PD6_120") (pintype "passive"))
    )
    (net (code "69") (name "/PD7") (class "Default")
      (node (ref "U14") (pin "121") (pinfunction "PD7_121") (pintype "passive"))
    )
    (net (code "70") (name "/PD8") (class "Default")
      (node (ref "SB103") (pin "1") (pinfunction "1_1") (pintype "passive"))
    )
    (net (code "71") (name "/PD9") (class "Default")
      (node (ref "SB104") (pin "1") (pinfunction "1_1") (pintype "passive"))
    )
    (net (code "72") (name "/PD10") (class "Default")
      (node (ref "JP8") (pin "2") (pinfunction "NO_2") (pintype "passive"))
      (node (ref "U14") (pin "78") (pinfunction "PD10_78") (pintype "passive"))
    )
    (net (code "73") (name "/PD11") (class "Default")
      (node (ref "U14") (pin "81") (pinfunction "PD11_81") (pintype "passive"))
    )
    (net (code "74") (name "/PD12") (class "Default")
      (node (ref "U14") (pin "82") (pinfunction "PD12_82") (pintype "passive"))
    )
    (net (code "75") (name "/PD13") (class "Default")
      (node (ref "U14") (pin "83") (pinfunction "PD13_83") (pintype "passive"))
    )
    (net (code "76") (name "/PD14") (class "Default")
      (node (ref "U14") (pin "84") (pinfunction "PD14_84") (pintype "passive"))
    )
    (net (code "77") (name "/PD15") (class "Default")
      (node (ref "U14") (pin "85") (pinfunction "PD15_85") (pintype "passive"))
    )
    (net (code "79") (name "/PE0") (class "Default")
      (node (ref "U14") (pin "138") (pinfunction "PE0_138") (pintype "passive"))
    )
    (net (code "80") (name "/PE1") (class "Default")
      (node (ref "U14") (pin "139") (pinfunction "PE1_139") (pintype "passive"))
    )
    (net (code "81") (name "/PE2") (class "Default")
      (node (ref "U14") (pin "1") (pinfunction "PE2_1") (pintype "passive"))
    )
    (net (code "82") (name "/PE3") (class "Default")
      (node (ref "U14") (pin "2") (pinfunction "PE3_2") (pintype "passive"))
    )
    (net (code "83") (name "/PE4") (class "Default")
      (node (ref "U14") (pin "3") (pinfunction "PE4_3") (pintype "passive"))
    )
    (net (code "84") (name "/PE5") (class "Default")
      (node (ref "U14") (pin "4") (pinfunction "PE5_4") (pintype "passive"))
    )
    (net (code "85") (name "/PE6") (class "Default")
      (node (ref "U14") (pin "5") (pinfunction "PE6_5") (pintype "passive"))
    )
    (net (code "86") (name "/PE7") (class "Default")
      (node (ref "U14") (pin "57") (pinfunction "PE7_57") (pintype "passive"))
    )
    (net (code "87") (name "/PE8") (class "Default")
      (node (ref "U14") (pin "58") (pinfunction "PE8_58") (pintype "passive"))
    )
    (net (code "88") (name "/PE9") (class "Default")
      (node (ref "U14") (pin "59") (pinfunction "PE9_59") (pintype "passive"))
    )
    (net (code "89") (name "/PE10") (class "Default")
      (node (ref "U14") (pin "60") (pinfunction "PE10_60") (pintype "passive"))
    )
    (net (code "90") (name "/PE11") (class "Default")
      (node (ref "U14") (pin "61") (pinfunction "PE11_61") (pintype "passive"))
    )
    (net (code "91") (name "/PE12") (class "Default")
      (node (ref "U14") (pin "62") (pinfunction "PE12_62") (pintype "passive"))
    )
    (net (code "92") (name "/PE13") (class "Default")
      (node (ref "U14") (pin "63") (pinfunction "PE13_63") (pintype "passive"))
    )
    (net (code "93") (name "/PE14") (class "Default")
      (node (ref "U14") (pin "64") (pinfunction "PE14_64") (pintype "passive"))
    )
    (net (code "94") (name "/PE15") (class "Default")
      (node (ref "U14") (pin "65") (pinfunction "PE15_65") (pintype "passive"))
    )
    (net (code "96") (name "/PF6") (class "Default")
      (node (ref "U14") (pin "20") (pinfunction "PF6_20") (pintype "passive"))
    )
    (net (code "97") (name "/PF7") (class "Default")
      (node (ref "U14") (pin "21") (pinfunction "PF7_21") (pintype "passive"))
    )
    (net (code "98") (name "/PF8") (class "Default")
      (node (ref "U14") (pin "22") (pinfunction "PF8_22") (pintype "passive"))
    )
    (net (code "99") (name "/PF9") (class "Default")
      (node (ref "U14") (pin "23") (pinfunction "PF9_23") (pintype "passive"))
    )
    (net (code "100") (name "/PF10") (class "Default")
      (node (ref "SB91") (pin "1") (pinfunction "1_1") (pintype "passive"))
      (node (ref "U14") (pin "24") (pinfunction "PF10_24") (pintype "passive"))
    )
    (net (code "101") (name "/PF11") (class "Default")
      (node (ref "U14") (pin "52") (pinfunction "PF11_52") (pintype "passive"))
    )
    (net (code "102") (name "/PF14") (class "Default")
      (node (ref "U14") (pin "53") (pinfunction "PF14_53") (pintype "passive"))
    )
    (net (code "103") (name "/PF15") (class "Default")
      (node (ref "U14") (pin "54") (pinfunction "PF15_54") (pintype "passive"))
    )
    (net (code "106") (name "/PG6") (class "Default")
      (node (ref "U14") (pin "86") (pinfunction "PG6_86") (pintype "passive"))
    )
    (net (code "107") (name "/PG7") (class "Default")
      (node (ref "SB100") (pin "2") (pinfunction "2_2") (pintype "passive"))
      (node (ref "U14") (pin "87") (pinfunction "PG7_87") (pintype "passive"))
    )
    (net (code "108") (name "/PG8") (class "Default")
      (node (ref "U14") (pin "88") (pinfunction "PG8_88") (pintype "passive"))
    )
    (net (code "109") (name "/PG9") (class "Default")
      (node (ref "U14") (pin "122") (pinfunction "PG9_122") (pintype "passive"))
    )
    (net (code "110") (name "/PG10") (class "Default")
      (node (ref "U14") (pin "123") (pinfunction "PG10_123") (pintype "passive"))
    )
    (net (code "111") (name "/PG11") (class "Default")
      (node (ref "SB36") (pin "2") (pinfunction "2_2") (pintype "passive"))
      (node (ref "U14") (pin "124") (pinfunction "PG11_124") (pintype "passive"))
    )
    (net (code "112") (name "/PG12") (class "Default")
      (node (ref "U14") (pin "125") (pinfunction "PG12_125") (pintype "passive"))
    )
    (net (code "113") (name "/PG13") (class "Default")
      (node (ref "SB46") (pin "2") (pinfunction "2_2") (pintype "passive"))
      (node (ref "U14") (pin "126") (pinfunction "PG13_126") (pintype "passive"))
    )
    (net (code "114") (name "/PG14") (class "Default")
      (node (ref "U14") (pin "127") (pinfunction "PG14_127") (pintype "passive"))
    )
    (net (code "116") (name "/PH0") (class "Default")
      (node (ref "SB71") (pin "2") (pinfunction "2_2") (pintype "passive"))
    )
    (net (code "117") (name "/PH0-MCU") (class "Default")
      (node (ref "SB3") (pin "1") (pinfunction "1_1") (pintype "passive"))
      (node (ref "SB71") (pin "1") (pinfunction "1_1") (pintype "passive"))
      (node (ref "SB72") (pin "1") (pinfunction "1_1") (pintype "passive"))
      (node (ref "U14") (pin "25") (pinfunction "PH0-OSC_IN_25") (pintype "passive"))
    )
    (net (code "118") (name "/PH1") (class "Default")
      (node (ref "SB90") (pin "2") (pinfunction "2_2") (pintype "passive"))
    )
    (net (code "119") (name "/PH1-MCU") (class "Default")
      (node (ref "SB4") (pin "1") (pinfunction "1_1") (pintype "passive"))
      (node (ref "SB90") (pin "1") (pinfunction "1_1") (pintype "passive"))
      (node (ref "U14") (pin "26") (pinfunction "PH1-OSC_OUT_26") (pintype "passive"))
    )
    (net (code "121") (name "/RMII_CRS_DV") (class "Default")
      (node (ref "SB52") (pin "2") (pinfunction "2_2") (pintype "passive"))
    )
    (net (code "122") (name "/RMII_MDC") (class "Default")
      (node (ref "SB84") (pin "1") (pinfunction "1_1") (pintype "passive"))
    )
    (net (code "123") (name "/RMII_MDIO") (class "Default")
      (node (ref "JP7") (pin "1") (pinfunction "COMMON_1") (pintype "passive"))
    )
    (net (code "124") (name "/RMII_REF_CLK") (class "Default")
      (node (ref "SB80") (pin "2") (pinfunction "2_2") (pintype "passive"))
    )
    (net (code "125") (name "/RMII_RXD0") (class "Default")
      (node (ref "SB63") (pin "1") (pinfunction "1_1") (pintype "passive"))
    )
    (net (code "126") (name "/RMII_RXD1") (class "Default")
      (node (ref "SB48") (pin "1") (pinfunction "1_1") (pintype "passive"))
    )
    (net (code "127") (name "/RMII_TXD0") (class "Default")
      (node (ref "SB46") (pin "1") (pinfunction "1_1") (pintype "passive"))
    )
    (net (code "128") (name "/RMII_TXD1") (class "Default")
      (node (ref "JP6") (pin "2") (pinfunction "NO_2") (pintype "passive"))
    )
    (net (code "129") (name "/RMII_TX_EN") (class "Default")
      (node (ref "SB36") (pin "1") (pinfunction "1_1") (pintype "passive"))
    )
    (net (code "130") (name "/STLK_MCO") (class "Default")
      (node (ref "SB72") (pin "2") (pinfunction "2_2") (pintype "passive"))
    )
    (net (code "131") (name "/SWO") (class "Default")
      (node (ref "SB50") (pin "1") (pinfunction "1_1") (pintype "passive"))
    )
    (net (code "132") (name "/T_VCP_RX") (class "Default")
      (node (ref "SB17") (pin "2") (pinfunction "2_2") (pintype "passive"))
      (node (ref "SB64") (pin "1") (pinfunction "1_1") (pintype "passive"))
    )
    (net (code "133") (name "/T_VCP_TX") (class "Default")
      (node (ref "SB12") (pin "1") (pinfunction "1_1") (pintype "passive"))
      (node (ref "SB16") (pin "2") (pinfunction "2_2") (pintype "passive"))
    )
    (net (code "134") (name "/USB_FS_ID") (class "Default")
      (node (ref "SB29") (pin "2") (pinfunction "2_2") (pintype "passive"))
    )
    (net (code "135") (name "/USB_FS_N") (class "Default")
      (node (ref "SB26") (pin "2") (pinfunction "2_2") (pintype "passive"))
    )
    (net (code "136") (name "/USB_FS_OVCR") (class "Default")
      (node (ref "SB100") (pin "1") (pinfunction "1_1") (pintype "passive"))
    )
    (net (code "137") (name "/USB_FS_P") (class "Default")
      (node (ref "SB27") (pin "2") (pinfunction "2_2") (pintype "passive"))
    )
    (net (code "138") (name "/USB_FS_PWR_EN") (class "Default")
      (node (ref "JP8") (pin "1") (pinfunction "COMMON_1") (pintype "passive"))
      (node (ref "SB91") (pin "2") (pinfunction "2_2") (pintype "passive"))
    )
    (net (code "139") (name "/USB_FS_VBUS") (class "Default")
      (node (ref "R63") (pin "1") (pinfunction "1_1") (pintype "passive"))
    )
    (net (code "140") (name "/WAKEUP_KEY") (class "Default")
      (node (ref "B1") (pin "3") (pinfunction "3_3") (pintype "passive"))
      (node (ref "B1") (pin "4") (pinfunction "4_4") (pintype "passive"))
      (node (ref "R67") (pin "2") (pinfunction "2_2") (pintype "passive"))
      (node (ref "R77") (pin "2") (pinfunction "2_2") (pintype "passive"))
      (node (ref "U23") (pin "1") (pinfunction "IO1_1") (pintype "passive"))
    )
    (net (code "141") (name "GND") (class "Default")
      (node (ref "B2") (pin "3") (pinfunction "3_3") (pintype "passive"))
      (node (ref "B2") (pin "4") (pinfunction "4_4") (pintype "passive"))
      (node (ref "C60") (pin "1") (pinfunction "1_1") (pintype "passive"))
      (node (ref "C66") (pin "1") (pinfunction "1_1") (pintype "passive"))
      (node (ref "C74") (pin "2") (pinfunction "2_2") (pintype "passive"))
      (node (ref "C76") (pin "2") (pinfunction "2_2") (pintype "passive"))
      (node (ref "C77") (pin "2") (pinfunction "2_2") (pintype "passive"))
      (node (ref "C78") (pin "2") (pinfunction "2_2") (pintype "passive"))
      (node (ref "R36") (pin "2") (pinfunction "2_2") (pintype "passive"))
      (node (ref "R38") (pin "2") (pinfunction "2_2") (pintype "passive"))
      (node (ref "R67") (pin "1") (pinfunction "1_1") (pintype "passive"))
      (node (ref "U20") (pin "2") (pinfunction "GND_2") (pintype "passive"))
      (node (ref "U23") (pin "2") (pinfunction "GND_2") (pintype "passive"))
      (node (ref "X2") (pin "2") (pinfunction "2_2") (pintype "passive"))
      (node (ref "X2") (pin "4") (pinfunction "4_4") (pintype "passive"))
    )
    (net (code "142") (name "Net-(C60-Pad2)") (class "Default")
      (node (ref "C60") (pin "2") (pinfunction "2_2") (pintype "passive"))
      (node (ref "R77") (pin "1") (pinfunction "1_1") (pintype "passive"))
      (node (ref "SB81") (pin "1") (pinfunction "1_1") (pintype "passive"))
      (node (ref "SB82") (pin "1") (pinfunction "1_1") (pintype "passive"))
    )
    (net (code "143") (name "Net-(R63-Pad2)") (class "Default")
      (node (ref "R63") (pin "2") (pinfunction "2_2") (pintype "passive"))
      (node (ref "SB21") (pin "2") (pinfunction "2_2") (pintype "passive"))
    )
    (net (code "144") (name "Net-(U14A-PDR_ON)") (class "Default")
      (node (ref "R37") (pin "1") (pinfunction "1_1") (pintype "passive"))
      (node (ref "R38") (pin "1") (pinfunction "1_1") (pintype "passive"))
      (node (ref "U14") (pin "142") (pinfunction "PDR_ON_142") (pintype "passive"))
    )
    (net (code "145") (name "Net-(U14B-PD8)") (class "Default")
      (node (ref "SB103") (pin "2") (pinfunction "2_2") (pintype "passive"))
      (node (ref "SB15") (pin "1") (pinfunction "1_1") (pintype "passive"))
      (node (ref "SB16") (pin "1") (pinfunction "1_1") (pintype "passive"))
      (node (ref "U14") (pin "76") (pinfunction "PD8_76") (pintype "passive"))
    )
    (net (code "146") (name "Net-(U14B-PD9)") (class "Default")
      (node (ref "SB104") (pin "2") (pinfunction "2_2") (pintype "passive"))
      (node (ref "SB17") (pin "1") (pinfunction "1_1") (pintype "passive"))
      (node (ref "SB94") (pin "1") (pinfunction "1_1") (pintype "passive"))
      (node (ref "U14") (pin "77") (pinfunction "PD9_77") (pintype "passive"))
    )
    (net (code "147") (name "VDD") (class "Default")
      (node (ref "B1") (pin "1") (pinfunction "1_1") (pintype "passive"))
      (node (ref "B1") (pin "2") (pinfunction "2_2") (pintype "passive"))
    )
    (net (code "148") (name "VDD_MCU") (class "Default")
      (node (ref "R37") (pin "2") (pinfunction "2_2") (pintype "passive"))
    )
  )
)
